# Button.net
KiCad netlist of a schematic drawn in Altium Designer
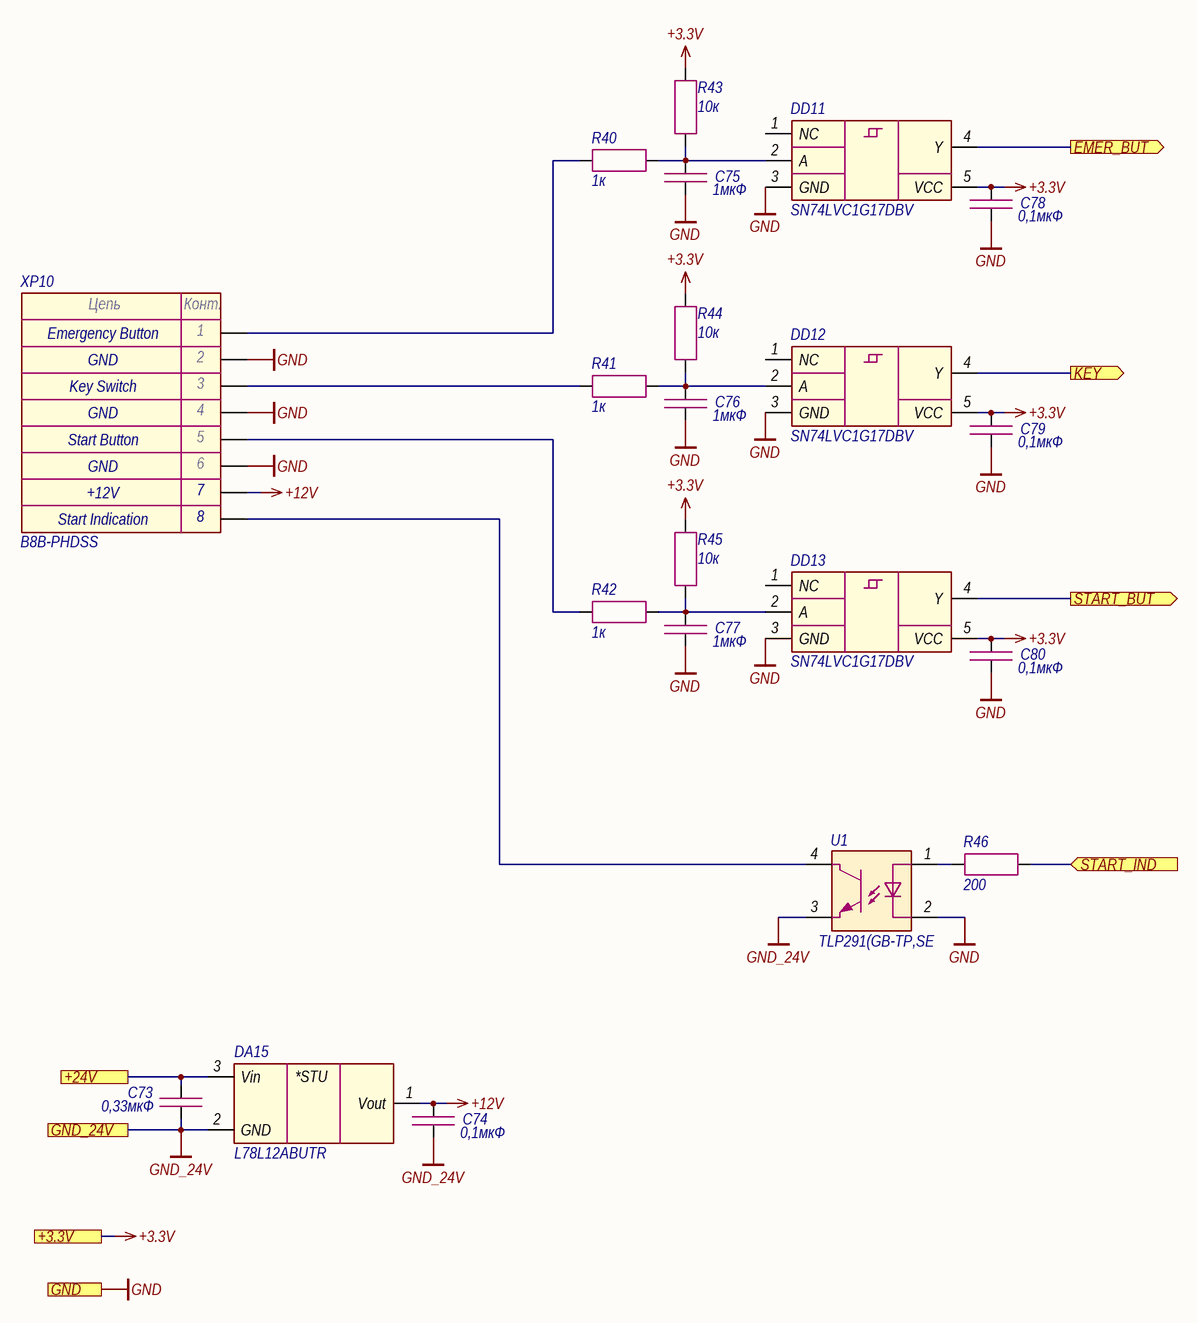
[diagram p0: Button.SchDoc]

(export (version "E")
  (design (tool "Eeschema 10.0.6"))
  (components
    (comp (ref "C73")
      (value "0,33мкФ")
      (footprint "Pcb_library:CAP_0805")
      (fields (field (name "MANUFACTURER") "Murata"))
      (libsource (lib "Schem_library") (part "Capacitor"))
    )
    (comp (ref "C74")
      (value "0,1мкФ")
      (footprint "Pcb_library:CAP_0603")
      (fields (field (name "MANUFACTURER") "Murata"))
      (libsource (lib "Schem_library") (part "Capacitor"))
    )
    (comp (ref "C75")
      (value "1мкФ")
      (footprint "Pcb_library:CAP_0603")
      (fields (field (name "MANUFACTURER") "Murata"))
      (libsource (lib "Schem_library") (part "Capacitor"))
    )
    (comp (ref "C76")
      (value "1мкФ")
      (footprint "Pcb_library:CAP_0603")
      (fields (field (name "MANUFACTURER") "Murata"))
      (libsource (lib "Schem_library") (part "Capacitor"))
    )
    (comp (ref "C77")
      (value "1мкФ")
      (footprint "Pcb_library:CAP_0603")
      (fields (field (name "MANUFACTURER") "Murata"))
      (libsource (lib "Schem_library") (part "Capacitor"))
    )
    (comp (ref "C78")
      (value "0,1мкФ")
      (footprint "Pcb_library:CAP_0603")
      (fields (field (name "MANUFACTURER") "Murata"))
      (libsource (lib "Schem_library") (part "Capacitor"))
    )
    (comp (ref "C79")
      (value "0,1мкФ")
      (footprint "Pcb_library:CAP_0603")
      (fields (field (name "MANUFACTURER") "Murata"))
      (libsource (lib "Schem_library") (part "Capacitor"))
    )
    (comp (ref "C80")
      (value "0,1мкФ")
      (footprint "Pcb_library:CAP_0603")
      (fields (field (name "MANUFACTURER") "Murata"))
      (libsource (lib "Schem_library") (part "Capacitor"))
    )
    (comp (ref "DA15")
      (value "L78L12ABUTR")
      (footprint "Pcb_library:SOT-89")
      (fields (field (name "MANUFACTURER") "STMicroelectronics"))
      (libsource (lib "Schem_library") (part "LD2981ABU50TR"))
    )
    (comp (ref "DD11")
      (value "SN74LVC1G17DBV")
      (footprint "Pcb_library:SOT-23-5")
      (fields (field (name "MANUFACTURER") "Texas Instruments"))
      (libsource (lib "Schem_library") (part "SN74LVC1G17"))
    )
    (comp (ref "DD12")
      (value "SN74LVC1G17DBV")
      (footprint "Pcb_library:SOT-23-5")
      (fields (field (name "MANUFACTURER") "Texas Instruments"))
      (libsource (lib "Schem_library") (part "SN74LVC1G17"))
    )
    (comp (ref "DD13")
      (value "SN74LVC1G17DBV")
      (footprint "Pcb_library:SOT-23-5")
      (fields (field (name "MANUFACTURER") "Texas Instruments"))
      (libsource (lib "Schem_library") (part "SN74LVC1G17"))
    )
    (comp (ref "R40")
      (value "1к")
      (footprint "Pcb_library:RES_0603")
      (fields (field (name "MANUFACTURER") "Yageo"))
      (libsource (lib "Schem_library") (part "Resistor"))
    )
    (comp (ref "R41")
      (value "1к")
      (footprint "Pcb_library:RES_0603")
      (fields (field (name "MANUFACTURER") "Yageo"))
      (libsource (lib "Schem_library") (part "Resistor"))
    )
    (comp (ref "R42")
      (value "1к")
      (footprint "Pcb_library:RES_0603")
      (fields (field (name "MANUFACTURER") "Yageo"))
      (libsource (lib "Schem_library") (part "Resistor"))
    )
    (comp (ref "R43")
      (value "10к")
      (footprint "Pcb_library:RES_0603")
      (fields (field (name "MANUFACTURER") "Yageo"))
      (libsource (lib "Schem_library") (part "Resistor"))
    )
    (comp (ref "R44")
      (value "10к")
      (footprint "Pcb_library:RES_0603")
      (fields (field (name "MANUFACTURER") "Yageo"))
      (libsource (lib "Schem_library") (part "Resistor"))
    )
    (comp (ref "R45")
      (value "10к")
      (footprint "Pcb_library:RES_0603")
      (fields (field (name "MANUFACTURER") "Yageo"))
      (libsource (lib "Schem_library") (part "Resistor"))
    )
    (comp (ref "R46")
      (value "200")
      (footprint "Pcb_library:RES_0603")
      (fields (field (name "MANUFACTURER") "Yageo"))
      (libsource (lib "Schem_library") (part "Resistor"))
    )
    (comp (ref "U1")
      (value "TLP291(GB-TP,SE")
      (footprint "Pcb_library:11-3C1")
      (fields (field (name "MANUFACTURER") "Toshiba"))
      (libsource (lib "Schem_library") (part "TLP291"))
    )
    (comp (ref "XP10")
      (value "B8B-PHDSS")
      (footprint "Pcb_library:B8B-PHDSS")
      (fields (field (name "MANUFACTURER") "JST"))
      (libsource (lib "Schem_library") (part "Connector-8"))
    )
  )
  (nets
    (net (code "1") (name "+3.3V") (class "Default")
      (node (ref "C78") (pin "1") (pinfunction "1_1") (pintype "passive"))
      (node (ref "C79") (pin "1") (pinfunction "1_1") (pintype "passive"))
      (node (ref "C80") (pin "1") (pinfunction "1_1") (pintype "passive"))
      (node (ref "DD11") (pin "5") (pinfunction "VCC_5") (pintype "passive"))
      (node (ref "DD12") (pin "5") (pinfunction "VCC_5") (pintype "passive"))
      (node (ref "DD13") (pin "5") (pinfunction "VCC_5") (pintype "passive"))
      (node (ref "R43") (pin "2") (pinfunction "2_2") (pintype "passive"))
      (node (ref "R44") (pin "2") (pinfunction "2_2") (pintype "passive"))
      (node (ref "R45") (pin "2") (pinfunction "2_2") (pintype "passive"))
    )
    (net (code "2") (name "+12V") (class "Default")
      (node (ref "C74") (pin "1") (pinfunction "1_1") (pintype "passive"))
      (node (ref "DA15") (pin "1") (pinfunction "Vout_1") (pintype "passive"))
      (node (ref "XP10") (pin "7") (pintype "passive"))
    )
    (net (code "3") (name "/+24V") (class "Default")
      (node (ref "C73") (pin "2") (pinfunction "2_2") (pintype "passive"))
      (node (ref "DA15") (pin "3") (pinfunction "Vin_3") (pintype "passive"))
    )
    (net (code "4") (name "/EMER_BUT") (class "Default")
      (node (ref "DD11") (pin "4") (pinfunction "Y_4") (pintype "passive"))
    )
    (net (code "5") (name "/KEY") (class "Default")
      (node (ref "DD12") (pin "4") (pinfunction "Y_4") (pintype "passive"))
    )
    (net (code "6") (name "/START_BUT") (class "Default")
      (node (ref "DD13") (pin "4") (pinfunction "Y_4") (pintype "passive"))
    )
    (net (code "7") (name "/START_IND") (class "Default")
      (node (ref "R46") (pin "2") (pinfunction "2_2") (pintype "passive"))
    )
    (net (code "8") (name "GND") (class "Default")
      (node (ref "C75") (pin "2") (pinfunction "2_2") (pintype "passive"))
      (node (ref "C76") (pin "2") (pinfunction "2_2") (pintype "passive"))
      (node (ref "C77") (pin "2") (pinfunction "2_2") (pintype "passive"))
      (node (ref "C78") (pin "2") (pinfunction "2_2") (pintype "passive"))
      (node (ref "C79") (pin "2") (pinfunction "2_2") (pintype "passive"))
      (node (ref "C80") (pin "2") (pinfunction "2_2") (pintype "passive"))
      (node (ref "DD11") (pin "3") (pinfunction "GND_3") (pintype "passive"))
      (node (ref "DD12") (pin "3") (pinfunction "GND_3") (pintype "passive"))
      (node (ref "DD13") (pin "3") (pinfunction "GND_3") (pintype "passive"))
      (node (ref "U1") (pin "2") (pintype "passive"))
      (node (ref "XP10") (pin "2") (pintype "passive"))
      (node (ref "XP10") (pin "4") (pintype "passive"))
      (node (ref "XP10") (pin "6") (pintype "passive"))
    )
    (net (code "9") (name "GND_24V") (class "Default")
      (node (ref "C73") (pin "1") (pinfunction "1_1") (pintype "passive"))
      (node (ref "C74") (pin "2") (pinfunction "2_2") (pintype "passive"))
      (node (ref "DA15") (pin "2") (pinfunction "GND_2") (pintype "passive"))
      (node (ref "U1") (pin "3") (pintype "passive"))
    )
    (net (code "10") (name "Net-(DD11-A)") (class "Default")
      (node (ref "C75") (pin "1") (pinfunction "1_1") (pintype "passive"))
      (node (ref "DD11") (pin "2") (pinfunction "A_2") (pintype "passive"))
      (node (ref "R40") (pin "2") (pinfunction "2_2") (pintype "passive"))
      (node (ref "R43") (pin "1") (pinfunction "1_1") (pintype "passive"))
    )
    (net (code "11") (name "Net-(DD12-A)") (class "Default")
      (node (ref "C76") (pin "1") (pinfunction "1_1") (pintype "passive"))
      (node (ref "DD12") (pin "2") (pinfunction "A_2") (pintype "passive"))
      (node (ref "R41") (pin "2") (pinfunction "2_2") (pintype "passive"))
      (node (ref "R44") (pin "1") (pinfunction "1_1") (pintype "passive"))
    )
    (net (code "12") (name "Net-(DD13-A)") (class "Default")
      (node (ref "C77") (pin "1") (pinfunction "1_1") (pintype "passive"))
      (node (ref "DD13") (pin "2") (pinfunction "A_2") (pintype "passive"))
      (node (ref "R42") (pin "2") (pinfunction "2_2") (pintype "passive"))
      (node (ref "R45") (pin "1") (pinfunction "1_1") (pintype "passive"))
    )
    (net (code "13") (name "Net-(R40-Pad1)") (class "Default")
      (node (ref "R40") (pin "1") (pinfunction "1_1") (pintype "passive"))
      (node (ref "XP10") (pin "1") (pintype "passive"))
    )
    (net (code "14") (name "Net-(R41-Pad1)") (class "Default")
      (node (ref "R41") (pin "1") (pinfunction "1_1") (pintype "passive"))
      (node (ref "XP10") (pin "3") (pintype "passive"))
    )
    (net (code "15") (name "Net-(R42-Pad1)") (class "Default")
      (node (ref "R42") (pin "1") (pinfunction "1_1") (pintype "passive"))
      (node (ref "XP10") (pin "5") (pintype "passive"))
    )
    (net (code "16") (name "Net-(R46-Pad1)") (class "Default")
      (node (ref "R46") (pin "1") (pinfunction "1_1") (pintype "passive"))
      (node (ref "U1") (pin "1") (pintype "passive"))
    )
    (net (code "17") (name "Net-(U1-Pad4)") (class "Default")
      (node (ref "U1") (pin "4") (pintype "passive"))
      (node (ref "XP10") (pin "8") (pintype "passive"))
    )
    (net (code "18") (name "unconnected-(DD11-NC-Pad1)") (class "Default")
      (node (ref "DD11") (pin "1") (pinfunction "NC_1") (pintype "passive"))
    )
    (net (code "19") (name "unconnected-(DD12-NC-Pad1)") (class "Default")
      (node (ref "DD12") (pin "1") (pinfunction "NC_1") (pintype "passive"))
    )
    (net (code "20") (name "unconnected-(DD13-NC-Pad1)") (class "Default")
      (node (ref "DD13") (pin "1") (pinfunction "NC_1") (pintype "passive"))
    )
  )
)
